# DC_Offset.net
KiCad netlist of a schematic drawn in EAGLE
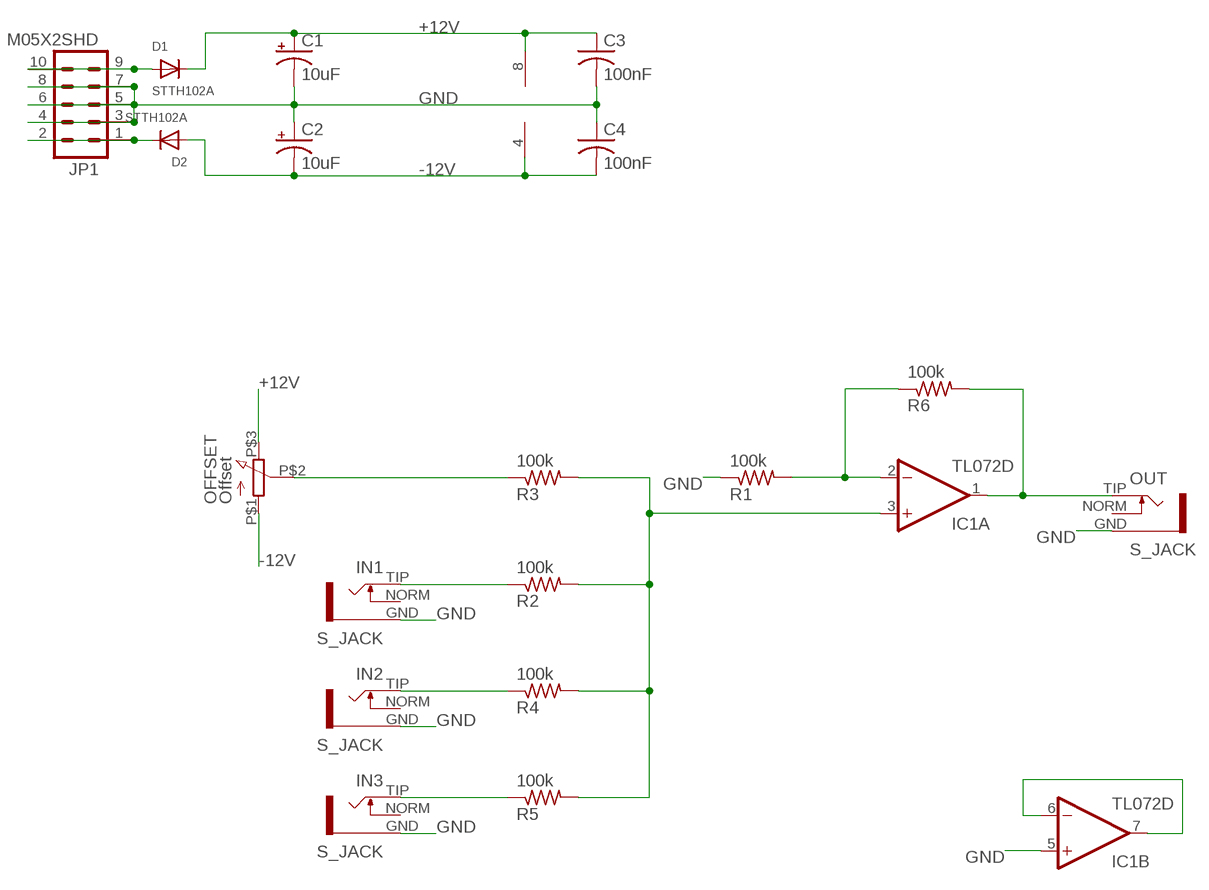
[diagram p0: schematic, sheet 1]

(export (version "E")
  (design (tool "Eeschema 10.0.6"))
  (components
    (comp (ref "C1")
      (value "10uF")
      (footprint "eagle-import:153CLV-0505")
      (libsource (lib "eagle-import") (part "CPOL-US153CLV-0505"))
    )
    (comp (ref "C2")
      (value "10uF")
      (footprint "eagle-import:153CLV-0505")
      (libsource (lib "eagle-import") (part "CPOL-US153CLV-0505"))
    )
    (comp (ref "C3")
      (value "100nF")
      (footprint "eagle-import:C0805")
      (libsource (lib "eagle-import") (part "C-USC0805"))
    )
    (comp (ref "C4")
      (value "100nF")
      (footprint "eagle-import:C0805")
      (libsource (lib "eagle-import") (part "C-USC0805"))
    )
    (comp (ref "D1")
      (value "STTH102A")
      (footprint "eagle-import:SMADIODE")
      (libsource (lib "eagle-import") (part "DIODESMA"))
    )
    (comp (ref "D2")
      (value "STTH102A")
      (footprint "eagle-import:SMADIODE")
      (libsource (lib "eagle-import") (part "DIODESMA"))
    )
    (comp (ref "IC1")
      (value "TL072D")
      (footprint "eagle-import:SO08")
      (libsource (lib "eagle-import") (part "TL072D"))
    )
    (comp (ref "IN1")
      (value "S_JACK")
      (footprint "eagle-import:S_JACK")
      (libsource (lib "eagle-import") (part "S_JACK"))
    )
    (comp (ref "IN2")
      (value "S_JACK")
      (footprint "eagle-import:S_JACK")
      (libsource (lib "eagle-import") (part "S_JACK"))
    )
    (comp (ref "IN3")
      (value "S_JACK")
      (footprint "eagle-import:S_JACK")
      (libsource (lib "eagle-import") (part "S_JACK"))
    )
    (comp (ref "JP1")
      (value "M05X2SHD")
      (footprint "eagle-import:2X5-SHROUDED")
      (libsource (lib "eagle-import") (part "M05X2SHD"))
    )
    (comp (ref "OFFSET")
      (value "Offset")
      (footprint "eagle-import:Q-POT")
      (libsource (lib "eagle-import") (part "Q-POT"))
    )
    (comp (ref "OUT")
      (value "S_JACK")
      (footprint "eagle-import:S_JACK")
      (libsource (lib "eagle-import") (part "S_JACK"))
    )
    (comp (ref "R1")
      (value "100k")
      (footprint "eagle-import:R0805")
      (libsource (lib "eagle-import") (part "R-US_R0805"))
    )
    (comp (ref "R2")
      (value "100k")
      (footprint "eagle-import:R0805")
      (libsource (lib "eagle-import") (part "R-US_R0805"))
    )
    (comp (ref "R3")
      (value "100k")
      (footprint "eagle-import:R0805")
      (libsource (lib "eagle-import") (part "R-US_R0805"))
    )
    (comp (ref "R4")
      (value "100k")
      (footprint "eagle-import:R0805")
      (libsource (lib "eagle-import") (part "R-US_R0805"))
    )
    (comp (ref "R5")
      (value "100k")
      (footprint "eagle-import:R0805")
      (libsource (lib "eagle-import") (part "R-US_R0805"))
    )
    (comp (ref "R6")
      (value "100k")
      (footprint "eagle-import:R0805")
      (libsource (lib "eagle-import") (part "R-US_R0805"))
    )
  )
  (nets
    (net (code "1") (name "/+12V") (class "Default")
      (node (ref "C1") (pin "+") (pinfunction "+_+") (pintype "passive"))
      (node (ref "C3") (pin "1") (pinfunction "1_1") (pintype "passive"))
      (node (ref "D1") (pin "C") (pinfunction "C_C") (pintype "passive"))
      (node (ref "IC1") (pin "8") (pinfunction "V+_8") (pintype "power_in"))
      (node (ref "OFFSET") (pin "P$3") (pinfunction "3_P$3") (pintype "passive"))
    )
    (net (code "2") (name "/-12V") (class "Default")
      (node (ref "C2") (pin "-") (pinfunction "-_-") (pintype "passive"))
      (node (ref "C4") (pin "2") (pinfunction "2_2") (pintype "passive"))
      (node (ref "D2") (pin "A") (pinfunction "A_A") (pintype "passive"))
      (node (ref "IC1") (pin "4") (pinfunction "V-_4") (pintype "power_in"))
      (node (ref "OFFSET") (pin "P$1") (pinfunction "1_P$1") (pintype "passive"))
    )
    (net (code "3") (name "/GND") (class "Default")
      (node (ref "C1") (pin "-") (pinfunction "-_-") (pintype "passive"))
      (node (ref "C2") (pin "+") (pinfunction "+_+") (pintype "passive"))
      (node (ref "C3") (pin "2") (pinfunction "2_2") (pintype "passive"))
      (node (ref "C4") (pin "1") (pinfunction "1_1") (pintype "passive"))
      (node (ref "IC1") (pin "5") (pinfunction "+IN_5") (pintype "input"))
      (node (ref "IN1") (pin "GND") (pinfunction "GND_GND") (pintype "passive"))
      (node (ref "IN2") (pin "GND") (pinfunction "GND_GND") (pintype "passive"))
      (node (ref "IN3") (pin "GND") (pinfunction "GND_GND") (pintype "passive"))
      (node (ref "JP1") (pin "3") (pinfunction "3_3") (pintype "passive"))
      (node (ref "JP1") (pin "4") (pinfunction "4_4") (pintype "passive"))
      (node (ref "JP1") (pin "5") (pinfunction "5_5") (pintype "passive"))
      (node (ref "JP1") (pin "6") (pinfunction "6_6") (pintype "passive"))
      (node (ref "JP1") (pin "7") (pinfunction "7_7") (pintype "passive"))
      (node (ref "JP1") (pin "8") (pinfunction "8_8") (pintype "passive"))
      (node (ref "OUT") (pin "GND") (pinfunction "GND_GND") (pintype "passive"))
      (node (ref "R1") (pin "1") (pinfunction "1_1") (pintype "passive"))
    )
    (net (code "4") (name "Net-(D1-PadA)") (class "Default")
      (node (ref "D1") (pin "A") (pinfunction "A_A") (pintype "passive"))
      (node (ref "JP1") (pin "10") (pinfunction "10_10") (pintype "passive"))
      (node (ref "JP1") (pin "9") (pinfunction "9_9") (pintype "passive"))
    )
    (net (code "5") (name "Net-(D2-PadC)") (class "Default")
      (node (ref "D2") (pin "C") (pinfunction "C_C") (pintype "passive"))
      (node (ref "JP1") (pin "1") (pinfunction "1_1") (pintype "passive"))
      (node (ref "JP1") (pin "2") (pinfunction "2_2") (pintype "passive"))
    )
    (net (code "6") (name "Net-(IC1A-+IN)") (class "Default")
      (node (ref "IC1") (pin "3") (pinfunction "+IN_3") (pintype "input"))
      (node (ref "R2") (pin "2") (pinfunction "2_2") (pintype "passive"))
      (node (ref "R3") (pin "2") (pinfunction "2_2") (pintype "passive"))
      (node (ref "R4") (pin "2") (pinfunction "2_2") (pintype "passive"))
      (node (ref "R5") (pin "2") (pinfunction "2_2") (pintype "passive"))
    )
    (net (code "7") (name "Net-(IC1A--IN)") (class "Default")
      (node (ref "IC1") (pin "2") (pinfunction "-IN_2") (pintype "input"))
      (node (ref "R1") (pin "2") (pinfunction "2_2") (pintype "passive"))
      (node (ref "R6") (pin "1") (pinfunction "1_1") (pintype "passive"))
    )
    (net (code "8") (name "Net-(IC1A-OUT)") (class "Default")
      (node (ref "IC1") (pin "1") (pinfunction "OUT_1") (pintype "output"))
      (node (ref "OUT") (pin "TIP") (pinfunction "TIP_TIP") (pintype "passive"))
      (node (ref "R6") (pin "2") (pinfunction "2_2") (pintype "passive"))
    )
    (net (code "9") (name "Net-(IC1B--IN)") (class "Default")
      (node (ref "IC1") (pin "6") (pinfunction "-IN_6") (pintype "input"))
      (node (ref "IC1") (pin "7") (pinfunction "OUT_7") (pintype "output"))
    )
    (net (code "10") (name "Net-(IN1-PadTIP)") (class "Default")
      (node (ref "IN1") (pin "TIP") (pinfunction "TIP_TIP") (pintype "passive"))
      (node (ref "R2") (pin "1") (pinfunction "1_1") (pintype "passive"))
    )
    (net (code "11") (name "Net-(IN2-PadTIP)") (class "Default")
      (node (ref "IN2") (pin "TIP") (pinfunction "TIP_TIP") (pintype "passive"))
      (node (ref "R4") (pin "1") (pinfunction "1_1") (pintype "passive"))
    )
    (net (code "12") (name "Net-(IN3-PadTIP)") (class "Default")
      (node (ref "IN3") (pin "TIP") (pinfunction "TIP_TIP") (pintype "passive"))
      (node (ref "R5") (pin "1") (pinfunction "1_1") (pintype "passive"))
    )
    (net (code "13") (name "Net-(OFFSET-2)") (class "Default")
      (node (ref "OFFSET") (pin "P$2") (pinfunction "2_P$2") (pintype "passive"))
      (node (ref "R3") (pin "1") (pinfunction "1_1") (pintype "passive"))
    )
    (net (code "14") (name "unconnected-(IN1-PadNORM)") (class "Default")
      (node (ref "IN1") (pin "NORM") (pinfunction "NORM_NORM") (pintype "passive"))
    )
    (net (code "15") (name "unconnected-(IN2-PadNORM)") (class "Default")
      (node (ref "IN2") (pin "NORM") (pinfunction "NORM_NORM") (pintype "passive"))
    )
    (net (code "16") (name "unconnected-(IN3-PadNORM)") (class "Default")
      (node (ref "IN3") (pin "NORM") (pinfunction "NORM_NORM") (pintype "passive"))
    )
    (net (code "17") (name "unconnected-(OUT-PadNORM)") (class "Default")
      (node (ref "OUT") (pin "NORM") (pinfunction "NORM_NORM") (pintype "passive"))
    )
  )
)
